# SCH_capacitor-dropper-power-supply_2024-.net
KiCad netlist of a schematic drawn in EasyEDA
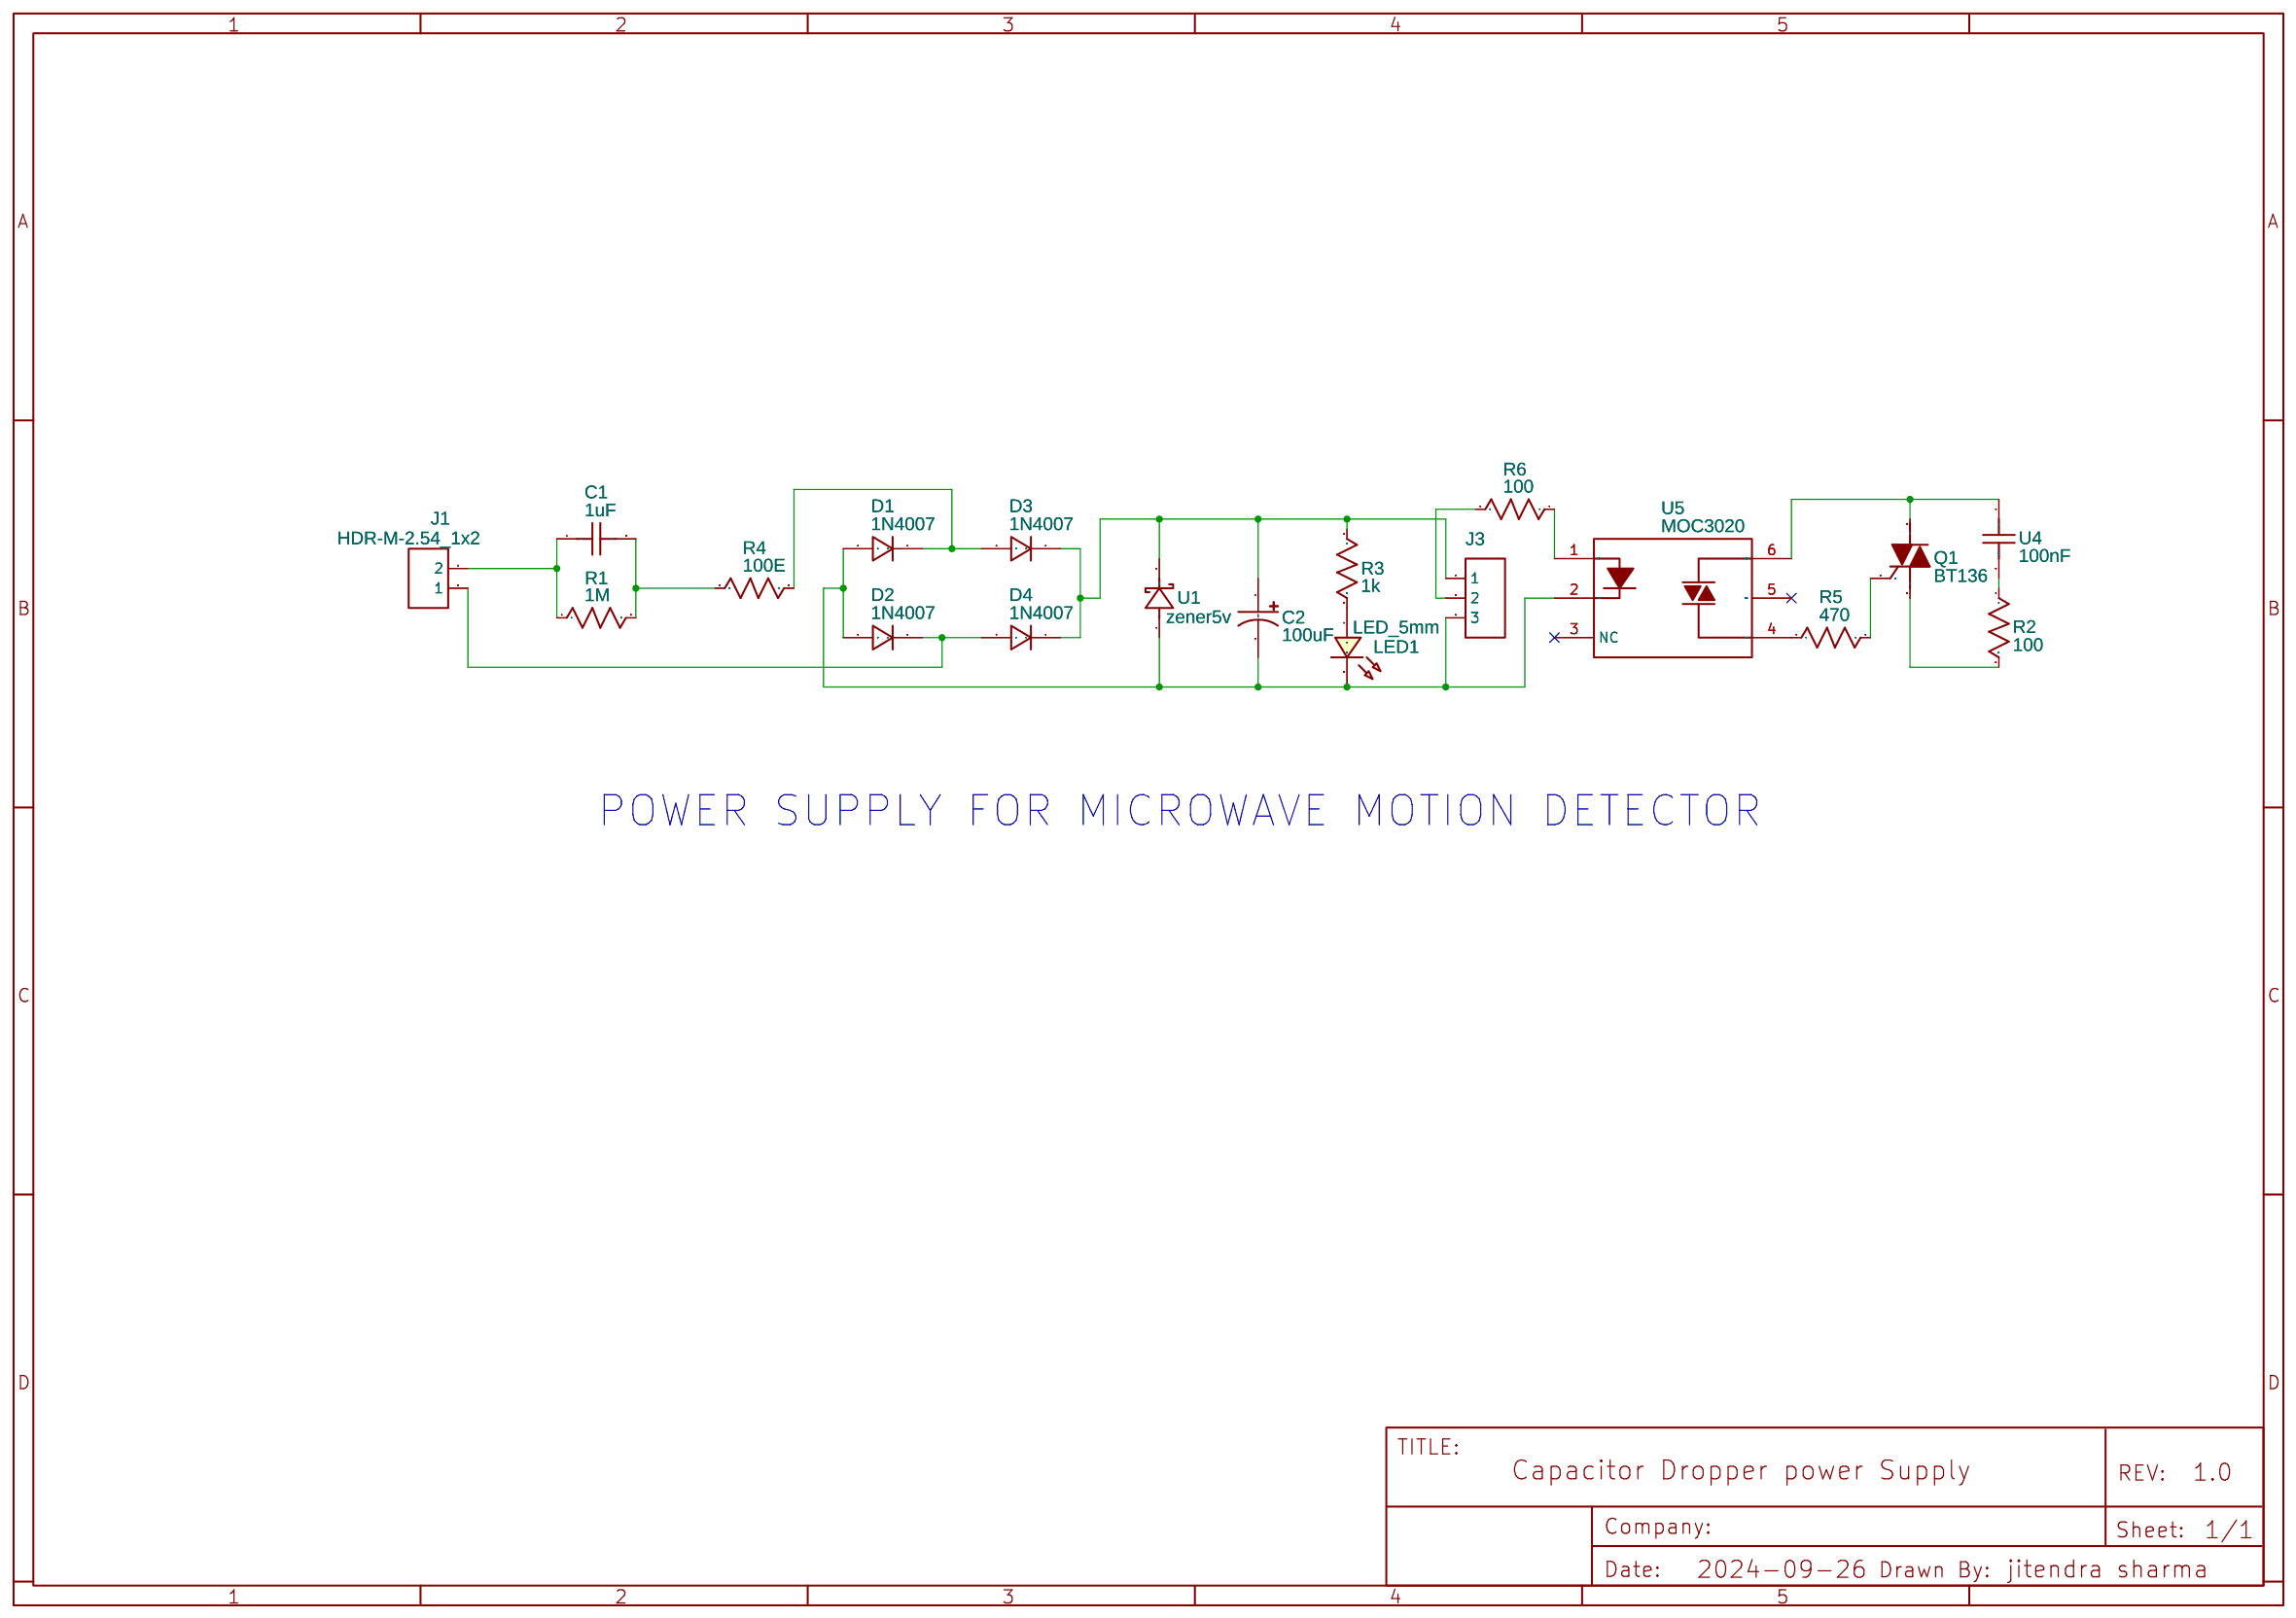
[diagram p0: schematic sheet]

(export (version "E")
  (design (tool "Eeschema 10.0.6"))
  (components
    (comp (ref "C1")
      (value "1uF")
      (fields (field (name "Manufacturer Part") "BFC237321105") (field (name "Manufacturer") "VISHAY(威世)"))
      (libsource (lib "") (part "BFC237321105"))
    )
    (comp (ref "C2")
      (value "100uF")
      (fields
        (field (name "Manufacturer Part") "KNE2100UF25V149EC0011")
        (field (name "Manufacturer") "KNSCHA(科尼盛)")
      )
      (libsource (lib "") (part "KNE2100UF25V149EC0011"))
    )
    (comp (ref "D1")
      (value "1N4007")
      (fields (field (name "Manufacturer") "SEMTECH"))
      (libsource (lib "") (part "1N4007"))
    )
    (comp (ref "D2")
      (value "1N4007")
      (fields (field (name "Manufacturer") "SEMTECH"))
      (libsource (lib "") (part "1N4007"))
    )
    (comp (ref "D3")
      (value "1N4007")
      (fields (field (name "Manufacturer") "SEMTECH"))
      (libsource (lib "") (part "1N4007"))
    )
    (comp (ref "D4")
      (value "1N4007")
      (fields (field (name "Manufacturer") "SEMTECH"))
      (libsource (lib "") (part "1N4007"))
    )
    (comp (ref "J1") (value "HDR-M-2.54_1x2") (libsource (lib "") (part "HDR-M-2.54_1x2")))
    (comp (ref "J3") (value "HDR-M-2.54_1x3") (libsource (lib "") (part "HDR-M-2.54_1x3")))
    (comp (ref "LED1")
      (value "LED_5mm")
      (fields
        (field (name "Manufacturer Part") "333-2SURD/S530-A3")
        (field (name "Manufacturer") "EVERLIGHT(台湾亿光)")
      )
      (libsource (lib "") (part "LED-TH-5mm_R"))
    )
    (comp (ref "Q1")
      (value "BT136")
      (fields (field (name "Manufacturer") "CJ(江苏长电/长晶)"))
      (libsource (lib "") (part "BT136"))
    )
    (comp (ref "R1") (value "1M") (libsource (lib "") (part "R_AXIAL-0.4_US")))
    (comp (ref "R2") (value "100") (libsource (lib "") (part "R_AXIAL-0.3_US_2")))
    (comp (ref "R3") (value "1k") (libsource (lib "") (part "R_AXIAL-0.4_US_1")))
    (comp (ref "R4") (value "100E") (libsource (lib "") (part "R_AXIAL-0.5_US")))
    (comp (ref "R5") (value "470") (libsource (lib "") (part "R_AXIAL-0.3_US_1")))
    (comp (ref "R6") (value "100") (libsource (lib "") (part "R_AXIAL-0.3_US")))
    (comp (ref "U1")
      (value "zener5v")
      (fields (field (name "Manufacturer Part") "1N4007-DIODE"))
      (libsource (lib "") (part "1N4007-DIODE"))
    )
    (comp (ref "U4")
      (value "100nF")
      (fields
        (field (name "Manufacturer Part") "MEB104J100V82CB0018")
        (field (name "Manufacturer") "KNSCHA(科尼盛)")
      )
      (libsource (lib "") (part "MEB104J100V82CB0018"))
    )
    (comp (ref "U5")
      (value "MOC3020")
      (fields (field (name "Manufacturer") "LITEON(光宝)"))
      (libsource (lib "") (part "MOC3020"))
    )
  )
  (nets
    (net (code "1") (name "Net-(C1-Pad1)") (class "Default")
      (node (ref "C1") (pin "1") (pinfunction "1_1") (pintype "unspecified"))
      (node (ref "J1") (pin "2") (pinfunction "2_2") (pintype "unspecified"))
      (node (ref "R1") (pin "1") (pinfunction "1_1") (pintype "unspecified"))
    )
    (net (code "2") (name "Net-(C1-Pad2)") (class "Default")
      (node (ref "C1") (pin "2") (pinfunction "2_2") (pintype "unspecified"))
      (node (ref "R1") (pin "2") (pinfunction "2_2") (pintype "unspecified"))
      (node (ref "R4") (pin "1") (pinfunction "1_1") (pintype "unspecified"))
    )
    (net (code "3") (name "Net-(D1-Pad1)") (class "Default")
      (node (ref "D1") (pin "1") (pinfunction "1_1") (pintype "unspecified"))
      (node (ref "D3") (pin "2") (pinfunction "2_2") (pintype "unspecified"))
      (node (ref "R4") (pin "2") (pinfunction "2_2") (pintype "unspecified"))
    )
    (net (code "4") (name "Net-(D2-Pad1)") (class "Default")
      (node (ref "D2") (pin "1") (pinfunction "1_1") (pintype "unspecified"))
      (node (ref "D4") (pin "2") (pinfunction "2_2") (pintype "unspecified"))
      (node (ref "J1") (pin "1") (pinfunction "1_1") (pintype "unspecified"))
    )
    (net (code "5") (name "Net-(J3-Pad2)") (class "Default")
      (node (ref "J3") (pin "2") (pinfunction "2_2") (pintype "input"))
      (node (ref "R6") (pin "2") (pinfunction "2_2") (pintype "unspecified"))
    )
    (net (code "6") (name "Net-(LED1-Pad1)") (class "Default")
      (node (ref "LED1") (pin "1") (pinfunction "1_1") (pintype "unspecified"))
      (node (ref "R3") (pin "2") (pinfunction "2_2") (pintype "unspecified"))
    )
    (net (code "7") (name "Net-(Q1-G)") (class "Default")
      (node (ref "Q1") (pin "3") (pinfunction "G_3") (pintype "unspecified"))
      (node (ref "R5") (pin "2") (pinfunction "2_2") (pintype "unspecified"))
    )
    (net (code "8") (name "Net-(Q1-M1)") (class "Default")
      (node (ref "Q1") (pin "1") (pinfunction "M1_1") (pintype "unspecified"))
      (node (ref "R2") (pin "2") (pinfunction "2_2") (pintype "unspecified"))
    )
    (net (code "9") (name "Net-(Q1-M2)") (class "Default")
      (node (ref "Q1") (pin "2") (pinfunction "M2_2") (pintype "unspecified"))
      (node (ref "U4") (pin "1") (pinfunction "1_1") (pintype "unspecified"))
      (node (ref "U5") (pin "6") (pinfunction "Terminal__6") (pintype "unspecified"))
    )
    (net (code "10") (name "Net-(R2-Pad1)") (class "Default")
      (node (ref "R2") (pin "1") (pinfunction "1_1") (pintype "unspecified"))
      (node (ref "U4") (pin "2") (pinfunction "2_2") (pintype "unspecified"))
    )
    (net (code "11") (name "Net-(U1-A)") (class "Default")
      (node (ref "C2") (pin "2") (pinfunction "2_2") (pintype "unspecified"))
      (node (ref "D1") (pin "2") (pinfunction "2_2") (pintype "unspecified"))
      (node (ref "D2") (pin "2") (pinfunction "2_2") (pintype "unspecified"))
      (node (ref "J3") (pin "3") (pinfunction "3_3") (pintype "input"))
      (node (ref "LED1") (pin "2") (pinfunction "2_2") (pintype "unspecified"))
      (node (ref "U1") (pin "1") (pinfunction "A_1") (pintype "unspecified"))
      (node (ref "U5") (pin "2") (pinfunction "Cathode__2") (pintype "unspecified"))
    )
    (net (code "12") (name "Net-(U1-K)") (class "Default")
      (node (ref "C2") (pin "1") (pinfunction "1_1") (pintype "unspecified"))
      (node (ref "D3") (pin "1") (pinfunction "1_1") (pintype "unspecified"))
      (node (ref "D4") (pin "1") (pinfunction "1_1") (pintype "unspecified"))
      (node (ref "J3") (pin "1") (pinfunction "1_1") (pintype "input"))
      (node (ref "R3") (pin "1") (pinfunction "1_1") (pintype "unspecified"))
      (node (ref "U1") (pin "2") (pinfunction "K_2") (pintype "unspecified"))
    )
    (net (code "13") (name "Net-(U5-ANODE)") (class "Default")
      (node (ref "R6") (pin "1") (pinfunction "1_1") (pintype "unspecified"))
      (node (ref "U5") (pin "1") (pinfunction "ANODE_1") (pintype "unspecified"))
    )
    (net (code "14") (name "Net-(U5-_Terminal)") (class "Default")
      (node (ref "R5") (pin "1") (pinfunction "1_1") (pintype "unspecified"))
      (node (ref "U5") (pin "4") (pinfunction "_Terminal_4") (pintype "unspecified"))
    )
    (net (code "15") (name "unconnected-(U5-NC-Pad3)") (class "Default")
      (node (ref "U5") (pin "3") (pinfunction "NC_3") (pintype "unspecified+no_connect"))
    )
    (net (code "16") (name "unconnected-(U5-Substrate_-Pad5)") (class "Default")
      (node (ref "U5") (pin "5") (pinfunction "Substrate__5") (pintype "unspecified+no_connect"))
    )
  )
)
